# 12V_Buck.net
KiCad netlist of a schematic drawn in Altium Designer
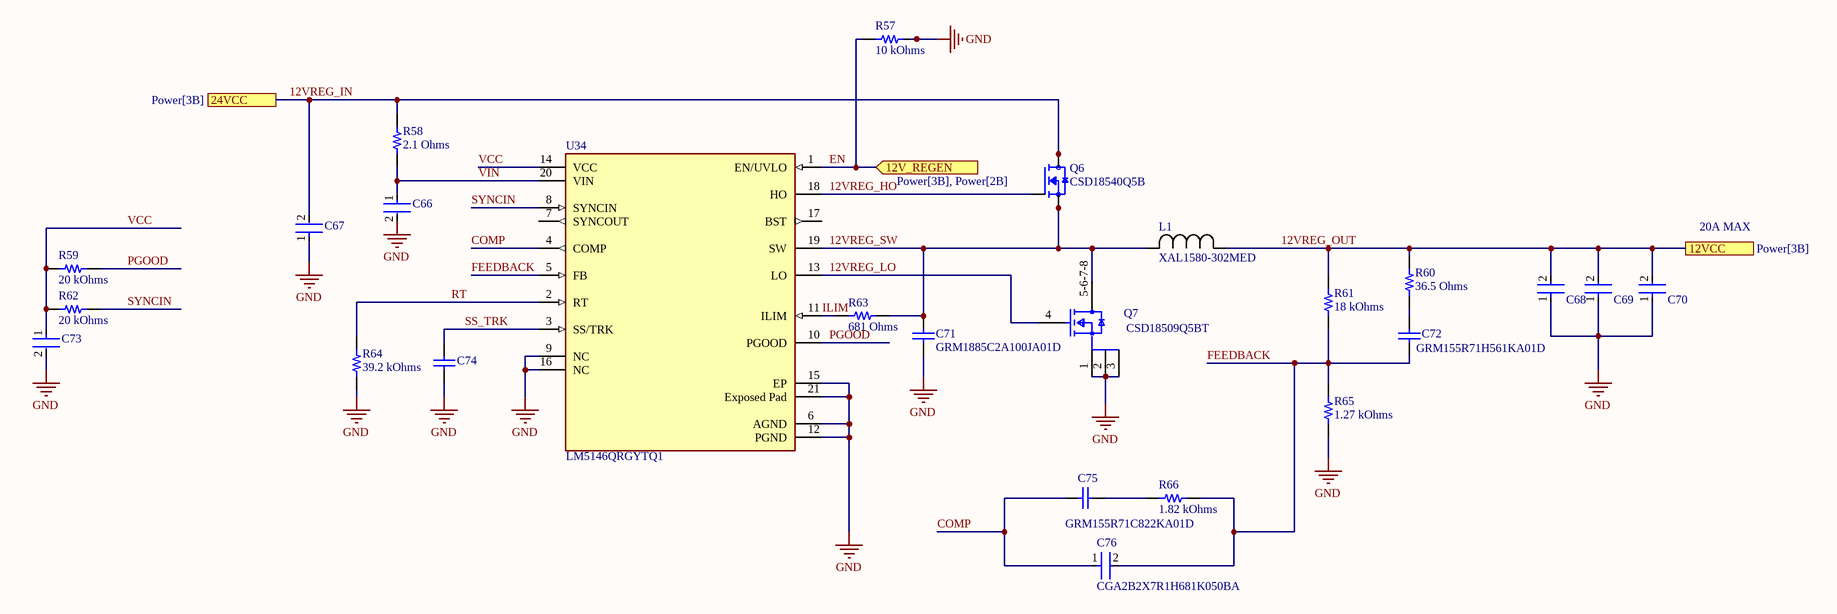
[diagram p0: 12V_Buck.SchDoc]

(export (version "E")
  (design (tool "Eeschema 10.0.6"))
  (components
    (comp (ref "C66")
      (value "CGA3E2X7R1H104K080AA")
      (footprint "FP-CGA3E-0_3-0_1-IPC_A")
      (description "Cap Ceramic 100nF 50V X7R 10% Pad SMD 0603 +125°C Automotive T/R")
      (fields (field (name "TOLERANCE") "10%") (field (name "VOLTAGE") "50V"))
      (libsource (lib "Altium Content Vault") (part "b4654b650e69147ec39a6b967a45e02"))
    )
    (comp (ref "C67")
      (value "GRM32ER71H475KA88L")
      (footprint "FP-GRM32-MFG")
      (description "CAP CER 4.7UF 50V X7R 1210")
      (fields (field (name "MANUFACTURER") "Murata") (field (name "TOLERANCE") "10%"))
      (libsource (lib "Altium Content Vault") (part "b4654b650e69147ec39a6b967a45e02"))
    )
    (comp (ref "C68")
      (value "GRM32ER61E226KE15L")
      (footprint "FP-GRM32-MFG")
      (description "CAP CER 22UF 25V X5R 1210")
      (fields
        (field (name "TOLERANCE") "10%")
        (field (name "MANUFACTURER") "Murata Electronics North America")
      )
      (libsource (lib "Altium Content Vault") (part "11868f565c42a9108669ba33697ecf6"))
    )
    (comp (ref "C69")
      (value "GRM32ER61E226KE15L")
      (footprint "FP-GRM32-MFG")
      (description "CAP CER 22UF 25V X5R 1210")
      (fields
        (field (name "TOLERANCE") "10%")
        (field (name "MANUFACTURER") "Murata Electronics North America")
      )
      (libsource (lib "Altium Content Vault") (part "11868f565c42a9108669ba33697ecf6"))
    )
    (comp (ref "C70")
      (value "GRM32ER61E226KE15L")
      (footprint "FP-GRM32-MFG")
      (description "CAP CER 22UF 25V X5R 1210")
      (fields
        (field (name "TOLERANCE") "10%")
        (field (name "MANUFACTURER") "Murata Electronics North America")
      )
      (libsource (lib "Altium Content Vault") (part "11868f565c42a9108669ba33697ecf6"))
    )
    (comp (ref "C71")
      (value "GRM1885C2A100JA01D")
      (footprint "CAPC1608X90X35LL10T15")
      (fields (field (name "MANUFACTURER") "Murata"))
      (libsource (lib "Altium Content Vault") (part "CAP"))
    )
    (comp (ref "C72")
      (value "GRM155R71H561KA01D")
      (footprint "CAPC1005X55X25LL05T10")
      (fields (field (name "MANUFACTURER") "Murata"))
      (libsource (lib "Altium Content Vault") (part "CAP"))
    )
    (comp (ref "C73")
      (value "C1005X5R1V225K050BC")
      (footprint "FP-C1005-050-0_15-IPC_A")
      (description "CAP CER 2.2UF 35V X5R 0402")
      (fields (field (name "TOLERANCE") "10%"))
      (libsource (lib "Altium Content Vault") (part "11868f565c42a9108669ba33697ecf6"))
    )
    (comp (ref "C74")
      (value "GRM155R71C563KA88D")
      (footprint "CAPC1005X55X25ML05T10")
      (fields (field (name "MANUFACTURER") "Murata"))
      (libsource (lib "Altium Content Vault") (part "CAP"))
    )
    (comp (ref "C75")
      (value "GRM155R71C822KA01D")
      (footprint "CAPC1005X55X25NL05T10")
      (fields (field (name "MANUFACTURER") "Murata"))
      (libsource (lib "Altium Content Vault") (part "CAP"))
    )
    (comp (ref "C76")
      (value "CGA2B2X7R1H681K050BA")
      (footprint "FP-CGA2B-IPC_C")
      (description "Cap Ceramic 680pF 50V X7R 10% Pad SMD 0402 +125°C Automotive T/R")
      (fields (field (name "TOLERANCE") "10%"))
      (libsource (lib "Altium Content Vault") (part "b4654b650e69147ec39a6b967a45e02"))
    )
    (comp (ref "L1")
      (value "XAL1580-302MED")
      (footprint "IND_XAL1580-302MED_COC")
      (description "No Description Available")
      (fields (field (name "COPYRIGHT") "Copyright (C) 2024 Ultra Librarian. All rights reserved."))
      (libsource (lib "XAL1580-302MED") (part "XAL1580-302MED"))
    )
    (comp (ref "Q6")
      (value "CSD18540Q5B")
      (footprint "TRANS_CSD18540Q5B")
      (description "60-V, N channel NexFETâ„¢ power MOSFET, single SON 5 mm x 6 mm, 2.2 mOhm")
      (fields (field (name "MF") "Texas Instruments"))
      (libsource (lib "CSD18540Q5B") (part "CSD18540Q5B"))
    )
    (comp (ref "Q7")
      (value "CSD18509Q5BT")
      (footprint "FP-DNK0008A-MFG")
      (description "MOSFET N-CH 40V 100A 8VSON")
      (libsource (lib "Altium Content Vault") (part "e3d99a1fa685e5f65b0a6aa31a0082f"))
    )
    (comp (ref "R57")
      (value "10 kOhms")
      (footprint "RES 0603_1608")
      (description "RES SMD 10K OHM 1% 1/10W 0603")
      (fields (field (name "PART NUMBER") "AA0603FR-0710KL") (field (name "MANUFACTURER") "Yageo"))
      (libsource (lib "altium_library") (part "Resistor"))
    )
    (comp (ref "R58")
      (value "2.1 Ohms")
      (footprint "RES 0603_1608")
      (description "RES SMD 2.1 OHM 1% 1/10W 0603")
      (fields (field (name "PART NUMBER") "CRCW06032R10FKEA") (field (name "MANUFACTURER") "Vishay Dale"))
      (libsource (lib "altium_library") (part "Resistor"))
    )
    (comp (ref "R59")
      (value "20 kOhms")
      (footprint "RES 0603_1608")
      (description "RES SMD 20K OHM 1% 1/10W 0603")
      (fields (field (name "PART NUMBER") "AC0603FR-0720KL") (field (name "MANUFACTURER") "Yageo"))
      (libsource (lib "altium_library") (part "Resistor"))
    )
    (comp (ref "R60")
      (value "36.5 Ohms")
      (footprint "RES 0603_1608")
      (description "RES SMD 36.5 OHM 1% 1/10W 0603")
      (fields (field (name "PART NUMBER") "CRCW060336R5FKEA") (field (name "MANUFACTURER") "Vishay Dale"))
      (libsource (lib "altium_library") (part "Resistor"))
    )
    (comp (ref "R61")
      (value "18 kOhms")
      (footprint "RES 0603_1608")
      (description "RES SMD 18K OHM 1% 1/10W 0603")
      (fields (field (name "PART NUMBER") "AC0603FR-0718KL") (field (name "MANUFACTURER") "Yageo"))
      (libsource (lib "altium_library") (part "Resistor"))
    )
    (comp (ref "R62")
      (value "20 kOhms")
      (footprint "RES 0603_1608")
      (description "RES SMD 20K OHM 1% 1/10W 0603")
      (fields (field (name "PART NUMBER") "AC0603FR-0720KL") (field (name "MANUFACTURER") "Yageo"))
      (libsource (lib "altium_library") (part "Resistor"))
    )
    (comp (ref "R63")
      (value "681 Ohms")
      (footprint "RES 0402_1005")
      (description "RES SMD 681 OHM 1% 1/10W 0402")
      (fields
        (field (name "PART NUMBER") "ERJ-2RKF6810X")
        (field (name "MANUFACTURER") "Panasonic Electronic Components")
      )
      (libsource (lib "altium_library") (part "Resistor"))
    )
    (comp (ref "R64")
      (value "39.2 kOhms")
      (footprint "RES 0603_1608")
      (description "RES SMD 39.2K OHM 0.1% 1/6W 0603")
      (fields
        (field (name "PART NUMBER") "5-2176089-3")
        (field (name "MANUFACTURER") "TE Connectivity Passive Product")
      )
      (libsource (lib "altium_library") (part "Resistor"))
    )
    (comp (ref "R65")
      (value "1.27 kOhms")
      (footprint "RES 0603_1608")
      (description "RES SMD 1.27K OHM 0.1% 1/6W 0603")
      (fields
        (field (name "PART NUMBER") "2-2176088-2")
        (field (name "MANUFACTURER") "TE Connectivity Passive Product")
      )
      (libsource (lib "altium_library") (part "Resistor"))
    )
    (comp (ref "R66")
      (value "1.82 kOhms")
      (footprint "RES 0603_1608")
      (description "RES SMD 1.82K OHM 1% 1/10W 0603")
      (fields (field (name "PART NUMBER") "AC0603FR-071K82L") (field (name "MANUFACTURER") "Yageo"))
      (libsource (lib "altium_library") (part "Resistor"))
    )
    (comp (ref "U34")
      (value "LM5146QRGYTQ1")
      (footprint "FP-RGY0020B-MFG")
      (description "IC REG BUCK ADJ 3.5A 20VQFN")
      (libsource (lib "Altium Content Vault") (part "8611d94e5be8735e787c8d9b4d0e1d9"))
    )
  )
  (nets
    (net (code "1") (name "/12VREG_HO") (class "Default")
      (node (ref "Q6") (pin "4") (pinfunction "G_4") (pintype "passive"))
      (node (ref "U34") (pin "18") (pinfunction "HO_18") (pintype "power_in"))
    )
    (net (code "2") (name "/12VREG_IN") (class "Default")
      (node (ref "C67") (pin "2") (pinfunction "2_2") (pintype "passive"))
      (node (ref "Q6") (pin "5") (pinfunction "D_5") (pintype "passive"))
      (node (ref "Q6") (pin "6") (pinfunction "D_6") (pintype "passive"))
      (node (ref "Q6") (pin "7") (pinfunction "D_7") (pintype "passive"))
      (node (ref "Q6") (pin "8") (pinfunction "D_8") (pintype "passive"))
      (node (ref "R58") (pin "2") (pinfunction "2_2") (pintype "passive"))
    )
    (net (code "3") (name "/12VREG_LO") (class "Default")
      (node (ref "Q7") (pin "4") (pinfunction "G_4") (pintype "passive"))
      (node (ref "U34") (pin "13") (pinfunction "LO_13") (pintype "power_in"))
    )
    (net (code "4") (name "/12VREG_OUT") (class "Default")
      (node (ref "C68") (pin "2") (pinfunction "2_2") (pintype "passive"))
      (node (ref "C69") (pin "2") (pinfunction "2_2") (pintype "passive"))
      (node (ref "C70") (pin "2") (pinfunction "2_2") (pintype "passive"))
      (node (ref "L1") (pin "1") (pinfunction "1_1") (pintype "passive"))
      (node (ref "R60") (pin "2") (pinfunction "2_2") (pintype "passive"))
      (node (ref "R61") (pin "2") (pinfunction "2_2") (pintype "passive"))
    )
    (net (code "5") (name "/12VREG_SW") (class "Default")
      (node (ref "C71") (pin "2") (pinfunction "2_2") (pintype "passive"))
      (node (ref "L1") (pin "2") (pinfunction "2_2") (pintype "passive"))
      (node (ref "Q6") (pin "1") (pinfunction "S_1") (pintype "passive"))
      (node (ref "Q6") (pin "2") (pinfunction "S_2") (pintype "passive"))
      (node (ref "Q6") (pin "3") (pinfunction "S_3") (pintype "passive"))
      (node (ref "Q7") (pin "5-6-7-8") (pinfunction "D_5-6-7-8") (pintype "passive"))
      (node (ref "R63") (pin "2") (pinfunction "2_2") (pintype "passive"))
      (node (ref "U34") (pin "19") (pinfunction "SW_19") (pintype "power_in"))
    )
    (net (code "6") (name "/COMP") (class "Default")
      (node (ref "C75") (pin "1") (pinfunction "1_1") (pintype "passive"))
      (node (ref "C76") (pin "1") (pinfunction "1_1") (pintype "passive"))
      (node (ref "U34") (pin "4") (pinfunction "COMP_4") (pintype "output"))
    )
    (net (code "7") (name "/EN") (class "Default")
      (node (ref "R57") (pin "1") (pinfunction "1_1") (pintype "passive"))
      (node (ref "U34") (pin "1") (pinfunction "EN/UVLO_1") (pintype "input"))
    )
    (net (code "8") (name "/FEEDBACK") (class "Default")
      (node (ref "C72") (pin "1") (pinfunction "1_1") (pintype "passive"))
      (node (ref "C76") (pin "2") (pinfunction "2_2") (pintype "passive"))
      (node (ref "R61") (pin "1") (pinfunction "1_1") (pintype "passive"))
      (node (ref "R65") (pin "2") (pinfunction "2_2") (pintype "passive"))
      (node (ref "R66") (pin "2") (pinfunction "2_2") (pintype "passive"))
      (node (ref "U34") (pin "5") (pinfunction "FB_5") (pintype "input"))
    )
    (net (code "9") (name "/ILIM") (class "Default")
      (node (ref "R63") (pin "1") (pinfunction "1_1") (pintype "passive"))
      (node (ref "U34") (pin "11") (pinfunction "ILIM_11") (pintype "input"))
    )
    (net (code "10") (name "/PGOOD") (class "Default")
      (node (ref "R59") (pin "2") (pinfunction "2_2") (pintype "passive"))
      (node (ref "U34") (pin "10") (pinfunction "PGOOD_10") (pintype "open_collector"))
    )
    (net (code "11") (name "/RT") (class "Default")
      (node (ref "R64") (pin "2") (pinfunction "2_2") (pintype "passive"))
      (node (ref "U34") (pin "2") (pinfunction "RT_2") (pintype "input"))
    )
    (net (code "12") (name "/SS_TRK") (class "Default")
      (node (ref "C74") (pin "2") (pinfunction "2_2") (pintype "passive"))
      (node (ref "U34") (pin "3") (pinfunction "SS/TRK_3") (pintype "input"))
    )
    (net (code "13") (name "/SYNCIN") (class "Default")
      (node (ref "R62") (pin "2") (pinfunction "2_2") (pintype "passive"))
      (node (ref "U34") (pin "8") (pinfunction "SYNCIN_8") (pintype "input"))
    )
    (net (code "14") (name "/VCC") (class "Default")
      (node (ref "C73") (pin "1") (pinfunction "1_1") (pintype "passive"))
      (node (ref "R59") (pin "1") (pinfunction "1_1") (pintype "passive"))
      (node (ref "R62") (pin "1") (pinfunction "1_1") (pintype "passive"))
      (node (ref "U34") (pin "14") (pinfunction "VCC_14") (pintype "power_in"))
    )
    (net (code "15") (name "/VIN") (class "Default")
      (node (ref "C66") (pin "1") (pinfunction "1_1") (pintype "passive"))
      (node (ref "R58") (pin "1") (pinfunction "1_1") (pintype "passive"))
      (node (ref "U34") (pin "20") (pinfunction "VIN_20") (pintype "power_in"))
    )
    (net (code "16") (name "GND") (class "Default")
      (node (ref "C66") (pin "2") (pinfunction "2_2") (pintype "passive"))
      (node (ref "C67") (pin "1") (pinfunction "1_1") (pintype "passive"))
      (node (ref "C68") (pin "1") (pinfunction "1_1") (pintype "passive"))
      (node (ref "C69") (pin "1") (pinfunction "1_1") (pintype "passive"))
      (node (ref "C70") (pin "1") (pinfunction "1_1") (pintype "passive"))
      (node (ref "C71") (pin "1") (pinfunction "1_1") (pintype "passive"))
      (node (ref "C73") (pin "2") (pinfunction "2_2") (pintype "passive"))
      (node (ref "C74") (pin "1") (pinfunction "1_1") (pintype "passive"))
      (node (ref "Q7") (pin "1") (pinfunction "S_1") (pintype "passive"))
      (node (ref "Q7") (pin "2") (pinfunction "S_2") (pintype "passive"))
      (node (ref "Q7") (pin "3") (pinfunction "S_3") (pintype "passive"))
      (node (ref "R57") (pin "2") (pinfunction "2_2") (pintype "passive"))
      (node (ref "R64") (pin "1") (pinfunction "1_1") (pintype "passive"))
      (node (ref "R65") (pin "1") (pinfunction "1_1") (pintype "passive"))
      (node (ref "U34") (pin "12") (pinfunction "PGND_12") (pintype "power_in"))
      (node (ref "U34") (pin "15") (pinfunction "EP_15") (pintype "power_in"))
      (node (ref "U34") (pin "16") (pinfunction "NC_16") (pintype "passive"))
      (node (ref "U34") (pin "21") (pinfunction "Exposed_Pad_21") (pintype "power_in"))
      (node (ref "U34") (pin "6") (pinfunction "AGND_6") (pintype "power_in"))
      (node (ref "U34") (pin "9") (pinfunction "NC_9") (pintype "passive"))
    )
    (net (code "17") (name "Net-(C72-Pad2)") (class "Default")
      (node (ref "C72") (pin "2") (pinfunction "2_2") (pintype "passive"))
      (node (ref "R60") (pin "1") (pinfunction "1_1") (pintype "passive"))
    )
    (net (code "18") (name "Net-(C75-Pad2)") (class "Default")
      (node (ref "C75") (pin "2") (pinfunction "2_2") (pintype "passive"))
      (node (ref "R66") (pin "1") (pinfunction "1_1") (pintype "passive"))
    )
    (net (code "19") (name "unconnected-(U34-BST-Pad17)") (class "Default")
      (node (ref "U34") (pin "17") (pinfunction "BST_17") (pintype "output"))
    )
    (net (code "20") (name "unconnected-(U34-SYNCOUT-Pad7)") (class "Default")
      (node (ref "U34") (pin "7") (pinfunction "SYNCOUT_7") (pintype "output"))
    )
  )
)
